# avr_programming_shield_Zif-Ken.net
KiCad netlist of a schematic drawn in EAGLE
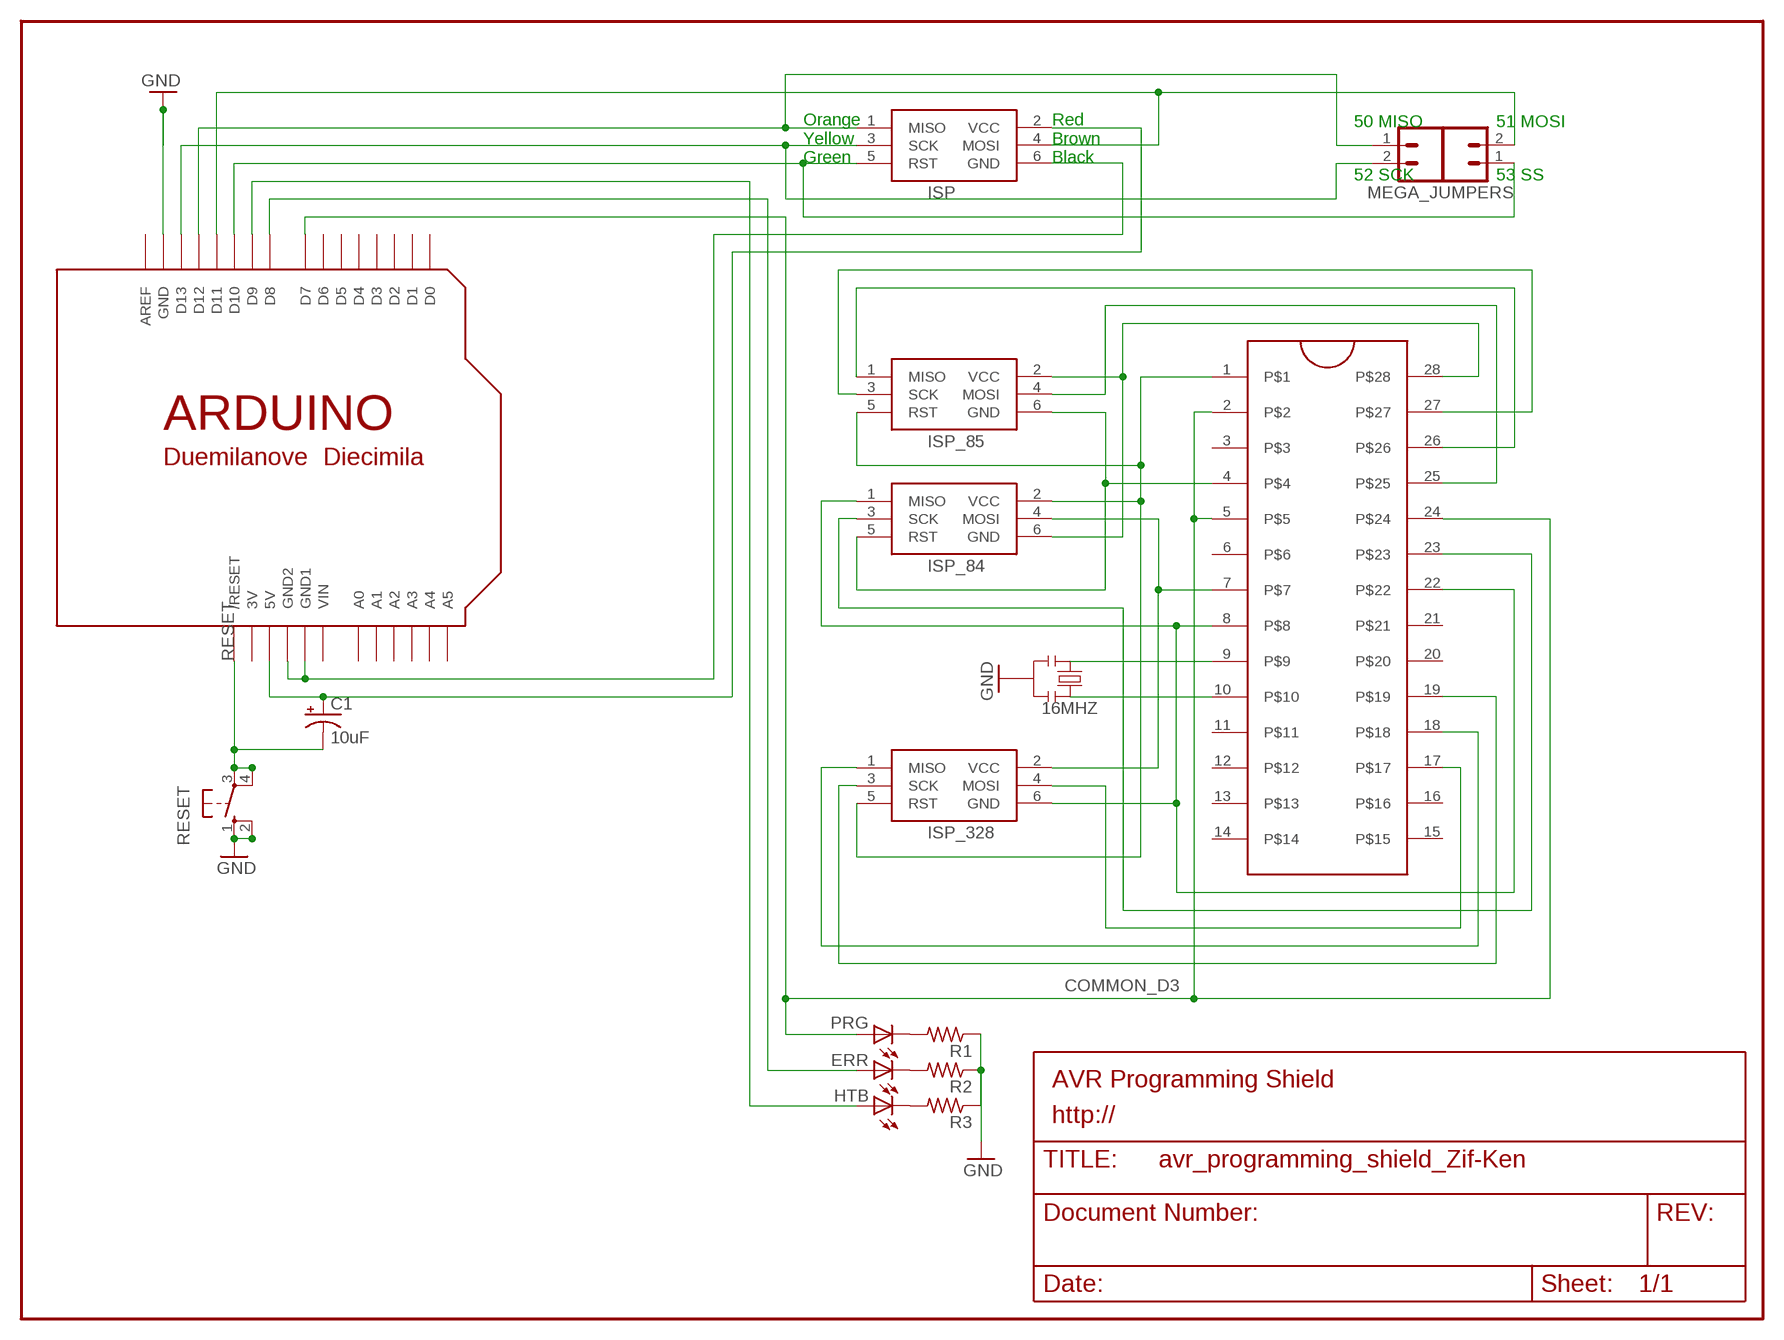
[diagram p0: schematic, sheet 1]

(export (version "E")
  (design (tool "Eeschema 10.0.6"))
  (components
    (comp (ref "16MHZ")
      (value "RESONATORPTH")
      (footprint "eagle-import:RESONATOR-PTH")
      (libsource (lib "eagle-import") (part "RESONATORPTH"))
    )
    (comp (ref "C1")
      (value "10uF")
      (footprint "eagle-import:CPOL-RADIAL-10UF-25V")
      (libsource (lib "eagle-import") (part "CAP_POLPTH2"))
    )
    (comp (ref "ERR")
      (value "LED3MM")
      (footprint "eagle-import:LED3MM")
      (libsource (lib "eagle-import") (part "LED3MM"))
    )
    (comp (ref "HTB")
      (value "LED3MM")
      (footprint "eagle-import:LED3MM")
      (libsource (lib "eagle-import") (part "LED3MM"))
    )
    (comp (ref "ISP")
      (value "AVRISP-6")
      (footprint "eagle-import:AVRISP")
      (libsource (lib "eagle-import") (part "AVRISP-6"))
    )
    (comp (ref "ISP_84")
      (value "AVRISP-6")
      (footprint "eagle-import:AVRISP")
      (libsource (lib "eagle-import") (part "AVRISP-6"))
    )
    (comp (ref "ISP_85")
      (value "AVRISP-6")
      (footprint "eagle-import:AVRISP")
      (libsource (lib "eagle-import") (part "AVRISP-6"))
    )
    (comp (ref "ISP_328")
      (value "AVRISP-6")
      (footprint "eagle-import:AVRISP")
      (libsource (lib "eagle-import") (part "AVRISP-6"))
    )
    (comp (ref "JP2")
      (value "M02PTH")
      (footprint "eagle-import:1X02")
      (libsource (lib "eagle-import") (part "M02PTH"))
    )
    (comp (ref "MEGA_JUMPERS")
      (value "M02PTH")
      (footprint "eagle-import:1X02")
      (libsource (lib "eagle-import") (part "M02PTH"))
    )
    (comp (ref "PRG")
      (value "LED3MM")
      (footprint "eagle-import:LED3MM")
      (libsource (lib "eagle-import") (part "LED3MM"))
    )
    (comp (ref "R1")
      (value "R-US_0204/2V")
      (footprint "eagle-import:0204V")
      (libsource (lib "eagle-import") (part "R-US_0204/2V"))
    )
    (comp (ref "R2")
      (value "R-US_0204/2V")
      (footprint "eagle-import:0204V")
      (libsource (lib "eagle-import") (part "R-US_0204/2V"))
    )
    (comp (ref "R3")
      (value "R-US_0204/2V")
      (footprint "eagle-import:0204V")
      (libsource (lib "eagle-import") (part "R-US_0204/2V"))
    )
    (comp (ref "RESET")
      (value "10-XX")
      (footprint "eagle-import:B3F-10XX")
      (libsource (lib "eagle-import") (part "10-XX"))
    )
    (comp (ref "U$1")
      (value "ARDUINO-NOHOLE")
      (footprint "eagle-import:ARDUINO-NOHOLE")
      (libsource (lib "eagle-import") (part "ARDUINO-NOHOLE"))
    )
    (comp (ref "U$3")
      (value "ZIFSOCKET-28-3ZIFFSOCKET-28-3")
      (footprint "eagle-import:DIL28-3-ZIF_SOCKET")
      (libsource (lib "eagle-import") (part "ZIFSOCKET-28-3ZIFFSOCKET-28-3"))
    )
  )
  (nets
    (net (code "1") (name "/3V") (class "Default")
      (node (ref "U$1") (pin "3V") (pinfunction "3V_3V") (pintype "power_in"))
    )
    (net (code "2") (name "/COMMON_D3") (class "Default")
      (node (ref "PRG") (pin "A") (pinfunction "A_A") (pintype "passive"))
      (node (ref "U$1") (pin "D7") (pinfunction "D7_D7") (pintype "bidirectional"))
      (node (ref "U$3") (pin "2") (pinfunction "P$2_2") (pintype "bidirectional"))
      (node (ref "U$3") (pin "24") (pinfunction "P$24_24") (pintype "bidirectional"))
      (node (ref "U$3") (pin "5") (pinfunction "P$5_5") (pintype "bidirectional"))
    )
    (net (code "3") (name "/RESET") (class "Default")
      (node (ref "C1") (pin "2") (pinfunction "-_2") (pintype "passive"))
      (node (ref "RESET") (pin "3") (pinfunction "P_3") (pintype "passive"))
      (node (ref "RESET") (pin "4") (pinfunction "P1_4") (pintype "passive"))
      (node (ref "U$1") (pin "RESET") (pinfunction "/RESET_RESET") (pintype "bidirectional"))
    )
    (net (code "4") (name "/VIN") (class "Default")
      (node (ref "U$1") (pin "VIN") (pinfunction "VIN_VIN") (pintype "power_in"))
    )
    (net (code "5") (name "GND") (class "Default")
      (node (ref "16MHZ") (pin "2") (pinfunction "2_2") (pintype "passive"))
      (node (ref "ISP") (pin "6") (pinfunction "GND_6") (pintype "power_in"))
      (node (ref "R1") (pin "1") (pinfunction "1_1") (pintype "passive"))
      (node (ref "R2") (pin "1") (pinfunction "1_1") (pintype "passive"))
      (node (ref "R3") (pin "1") (pinfunction "1_1") (pintype "passive"))
      (node (ref "RESET") (pin "1") (pinfunction "S_1") (pintype "passive"))
      (node (ref "RESET") (pin "2") (pinfunction "S1_2") (pintype "passive"))
      (node (ref "U$1") (pin "GND") (pinfunction "GND_GND") (pintype "power_in"))
      (node (ref "U$1") (pin "GND1") (pinfunction "GND1_GND1") (pintype "power_in"))
      (node (ref "U$1") (pin "GND2") (pinfunction "GND2_GND2") (pintype "power_in"))
    )
    (net (code "6") (name "Net-(C1-+)") (class "Default")
      (node (ref "C1") (pin "1") (pinfunction "+_1") (pintype "passive"))
      (node (ref "ISP") (pin "2") (pinfunction "VCC_2") (pintype "power_in"))
      (node (ref "U$1") (pin "5V") (pinfunction "5V_5V") (pintype "power_in"))
    )
    (net (code "7") (name "Net-(ERR-C)") (class "Default")
      (node (ref "ERR") (pin "K") (pinfunction "C_K") (pintype "passive"))
      (node (ref "R2") (pin "2") (pinfunction "2_2") (pintype "passive"))
    )
    (net (code "8") (name "Net-(ERR-PadA)") (class "Default")
      (node (ref "ERR") (pin "A") (pinfunction "A_A") (pintype "passive"))
      (node (ref "U$1") (pin "D8") (pinfunction "D8_D8") (pintype "bidirectional"))
    )
    (net (code "9") (name "Net-(HTB-C)") (class "Default")
      (node (ref "HTB") (pin "K") (pinfunction "C_K") (pintype "passive"))
      (node (ref "R3") (pin "2") (pinfunction "2_2") (pintype "passive"))
    )
    (net (code "10") (name "Net-(HTB-PadA)") (class "Default")
      (node (ref "HTB") (pin "A") (pinfunction "A_A") (pintype "passive"))
      (node (ref "U$1") (pin "D9") (pinfunction "D9_D9") (pintype "bidirectional"))
    )
    (net (code "11") (name "Net-(ISP-MISO)") (class "Default")
      (node (ref "ISP") (pin "1") (pinfunction "MISO_1") (pintype "input"))
      (node (ref "MEGA_JUMPERS") (pin "1") (pinfunction "1_1") (pintype "passive"))
      (node (ref "U$1") (pin "D12") (pinfunction "D12_D12") (pintype "bidirectional"))
    )
    (net (code "12") (name "Net-(ISP-MOSI)") (class "Default")
      (node (ref "ISP") (pin "4") (pinfunction "MOSI_4") (pintype "output"))
      (node (ref "JP2") (pin "2") (pinfunction "2_2") (pintype "passive"))
      (node (ref "U$1") (pin "D11") (pinfunction "D11_D11") (pintype "bidirectional"))
    )
    (net (code "13") (name "Net-(ISP-RST)") (class "Default")
      (node (ref "ISP") (pin "5") (pinfunction "RST_5") (pintype "output"))
      (node (ref "JP2") (pin "1") (pinfunction "1_1") (pintype "passive"))
      (node (ref "U$1") (pin "D10") (pinfunction "D10_D10") (pintype "bidirectional"))
    )
    (net (code "14") (name "Net-(ISP-SCK)") (class "Default")
      (node (ref "ISP") (pin "3") (pinfunction "SCK_3") (pintype "output"))
      (node (ref "MEGA_JUMPERS") (pin "2") (pinfunction "2_2") (pintype "passive"))
      (node (ref "U$1") (pin "D13") (pinfunction "D13_D13") (pintype "bidirectional"))
    )
    (net (code "15") (name "Net-(ISP_84-GND)") (class "Default")
      (node (ref "ISP_84") (pin "6") (pinfunction "GND_6") (pintype "power_in"))
      (node (ref "ISP_85") (pin "2") (pinfunction "VCC_2") (pintype "power_in"))
      (node (ref "U$3") (pin "28") (pinfunction "P$28_28") (pintype "bidirectional"))
    )
    (net (code "16") (name "Net-(ISP_84-RST)") (class "Default")
      (node (ref "ISP_84") (pin "5") (pinfunction "RST_5") (pintype "output"))
      (node (ref "ISP_85") (pin "6") (pinfunction "GND_6") (pintype "power_in"))
      (node (ref "U$3") (pin "4") (pinfunction "P$4_4") (pintype "bidirectional"))
    )
    (net (code "17") (name "Net-(ISP_84-SCK)") (class "Default")
      (node (ref "ISP_84") (pin "3") (pinfunction "SCK_3") (pintype "output"))
      (node (ref "U$3") (pin "23") (pinfunction "P$23_23") (pintype "bidirectional"))
    )
    (net (code "18") (name "Net-(ISP_85-MISO)") (class "Default")
      (node (ref "ISP_85") (pin "1") (pinfunction "MISO_1") (pintype "input"))
      (node (ref "U$3") (pin "26") (pinfunction "P$26_26") (pintype "bidirectional"))
    )
    (net (code "19") (name "Net-(ISP_85-MOSI)") (class "Default")
      (node (ref "ISP_85") (pin "4") (pinfunction "MOSI_4") (pintype "output"))
      (node (ref "U$3") (pin "25") (pinfunction "P$25_25") (pintype "bidirectional"))
    )
    (net (code "20") (name "Net-(ISP_85-SCK)") (class "Default")
      (node (ref "ISP_85") (pin "3") (pinfunction "SCK_3") (pintype "output"))
      (node (ref "U$3") (pin "27") (pinfunction "P$27_27") (pintype "bidirectional"))
    )
    (net (code "21") (name "Net-(ISP_328-GND)") (class "Default")
      (node (ref "ISP_328") (pin "6") (pinfunction "GND_6") (pintype "power_in"))
      (node (ref "ISP_84") (pin "1") (pinfunction "MISO_1") (pintype "input"))
      (node (ref "U$3") (pin "22") (pinfunction "P$22_22") (pintype "bidirectional"))
      (node (ref "U$3") (pin "8") (pinfunction "P$8_8") (pintype "bidirectional"))
    )
    (net (code "22") (name "Net-(ISP_328-MISO)") (class "Default")
      (node (ref "ISP_328") (pin "1") (pinfunction "MISO_1") (pintype "input"))
      (node (ref "U$3") (pin "18") (pinfunction "P$18_18") (pintype "bidirectional"))
    )
    (net (code "23") (name "Net-(ISP_328-MOSI)") (class "Default")
      (node (ref "ISP_328") (pin "4") (pinfunction "MOSI_4") (pintype "output"))
      (node (ref "U$3") (pin "17") (pinfunction "P$17_17") (pintype "bidirectional"))
    )
    (net (code "24") (name "Net-(ISP_328-RST)") (class "Default")
      (node (ref "ISP_328") (pin "5") (pinfunction "RST_5") (pintype "output"))
      (node (ref "ISP_84") (pin "2") (pinfunction "VCC_2") (pintype "power_in"))
      (node (ref "ISP_85") (pin "5") (pinfunction "RST_5") (pintype "output"))
      (node (ref "U$3") (pin "1") (pinfunction "P$1_1") (pintype "bidirectional"))
    )
    (net (code "25") (name "Net-(ISP_328-SCK)") (class "Default")
      (node (ref "ISP_328") (pin "3") (pinfunction "SCK_3") (pintype "output"))
      (node (ref "U$3") (pin "19") (pinfunction "P$19_19") (pintype "bidirectional"))
    )
    (net (code "26") (name "Net-(ISP_328-VCC)") (class "Default")
      (node (ref "ISP_328") (pin "2") (pinfunction "VCC_2") (pintype "power_in"))
      (node (ref "ISP_84") (pin "4") (pinfunction "MOSI_4") (pintype "output"))
      (node (ref "U$3") (pin "7") (pinfunction "P$7_7") (pintype "bidirectional"))
    )
    (net (code "27") (name "Net-(PRG-C)") (class "Default")
      (node (ref "PRG") (pin "K") (pinfunction "C_K") (pintype "passive"))
      (node (ref "R1") (pin "2") (pinfunction "2_2") (pintype "passive"))
    )
    (net (code "28") (name "Net-(U$3-P$9)") (class "Default")
      (node (ref "16MHZ") (pin "1") (pinfunction "1_1") (pintype "passive"))
      (node (ref "U$3") (pin "9") (pinfunction "P$9_9") (pintype "bidirectional"))
    )
    (net (code "29") (name "Net-(U$3-P$10)") (class "Default")
      (node (ref "16MHZ") (pin "3") (pinfunction "3_3") (pintype "passive"))
      (node (ref "U$3") (pin "10") (pinfunction "P$10_10") (pintype "bidirectional"))
    )
    (net (code "30") (name "unconnected-(U$1-PadA0)") (class "Default")
      (node (ref "U$1") (pin "A0") (pinfunction "A0_A0") (pintype "bidirectional"))
    )
    (net (code "31") (name "unconnected-(U$1-PadA1)") (class "Default")
      (node (ref "U$1") (pin "A1") (pinfunction "A1_A1") (pintype "bidirectional"))
    )
    (net (code "32") (name "unconnected-(U$1-PadA2)") (class "Default")
      (node (ref "U$1") (pin "A2") (pinfunction "A2_A2") (pintype "bidirectional"))
    )
    (net (code "33") (name "unconnected-(U$1-PadA3)") (class "Default")
      (node (ref "U$1") (pin "A3") (pinfunction "A3_A3") (pintype "bidirectional"))
    )
    (net (code "34") (name "unconnected-(U$1-PadA4)") (class "Default")
      (node (ref "U$1") (pin "A4") (pinfunction "A4_A4") (pintype "bidirectional"))
    )
    (net (code "35") (name "unconnected-(U$1-PadA5)") (class "Default")
      (node (ref "U$1") (pin "A5") (pinfunction "A5_A5") (pintype "bidirectional"))
    )
    (net (code "36") (name "unconnected-(U$1-PadAREF)") (class "Default")
      (node (ref "U$1") (pin "AREF") (pinfunction "AREF_AREF") (pintype "bidirectional"))
    )
    (net (code "37") (name "unconnected-(U$1-PadD0)") (class "Default")
      (node (ref "U$1") (pin "D0") (pinfunction "D0_D0") (pintype "bidirectional"))
    )
    (net (code "38") (name "unconnected-(U$1-PadD1)") (class "Default")
      (node (ref "U$1") (pin "D1") (pinfunction "D1_D1") (pintype "bidirectional"))
    )
    (net (code "39") (name "unconnected-(U$1-PadD2)") (class "Default")
      (node (ref "U$1") (pin "D2") (pinfunction "D2_D2") (pintype "bidirectional"))
    )
    (net (code "40") (name "unconnected-(U$1-PadD3)") (class "Default")
      (node (ref "U$1") (pin "D3") (pinfunction "D3_D3") (pintype "bidirectional"))
    )
    (net (code "41") (name "unconnected-(U$1-PadD4)") (class "Default")
      (node (ref "U$1") (pin "D4") (pinfunction "D4_D4") (pintype "bidirectional"))
    )
    (net (code "42") (name "unconnected-(U$1-PadD5)") (class "Default")
      (node (ref "U$1") (pin "D5") (pinfunction "D5_D5") (pintype "bidirectional"))
    )
    (net (code "43") (name "unconnected-(U$1-PadD6)") (class "Default")
      (node (ref "U$1") (pin "D6") (pinfunction "D6_D6") (pintype "bidirectional"))
    )
    (net (code "44") (name "unconnected-(U$3-P$3-Pad3)") (class "Default")
      (node (ref "U$3") (pin "3") (pinfunction "P$3_3") (pintype "bidirectional"))
    )
    (net (code "45") (name "unconnected-(U$3-P$6-Pad6)") (class "Default")
      (node (ref "U$3") (pin "6") (pinfunction "P$6_6") (pintype "bidirectional"))
    )
    (net (code "46") (name "unconnected-(U$3-P$11-Pad11)") (class "Default")
      (node (ref "U$3") (pin "11") (pinfunction "P$11_11") (pintype "bidirectional"))
    )
    (net (code "47") (name "unconnected-(U$3-P$12-Pad12)") (class "Default")
      (node (ref "U$3") (pin "12") (pinfunction "P$12_12") (pintype "bidirectional"))
    )
    (net (code "48") (name "unconnected-(U$3-P$13-Pad13)") (class "Default")
      (node (ref "U$3") (pin "13") (pinfunction "P$13_13") (pintype "bidirectional"))
    )
    (net (code "49") (name "unconnected-(U$3-P$14-Pad14)") (class "Default")
      (node (ref "U$3") (pin "14") (pinfunction "P$14_14") (pintype "bidirectional"))
    )
    (net (code "50") (name "unconnected-(U$3-P$15-Pad15)") (class "Default")
      (node (ref "U$3") (pin "15") (pinfunction "P$15_15") (pintype "bidirectional"))
    )
    (net (code "51") (name "unconnected-(U$3-P$16-Pad16)") (class "Default")
      (node (ref "U$3") (pin "16") (pinfunction "P$16_16") (pintype "bidirectional"))
    )
    (net (code "52") (name "unconnected-(U$3-P$20-Pad20)") (class "Default")
      (node (ref "U$3") (pin "20") (pinfunction "P$20_20") (pintype "bidirectional"))
    )
    (net (code "53") (name "unconnected-(U$3-P$21-Pad21)") (class "Default")
      (node (ref "U$3") (pin "21") (pinfunction "P$21_21") (pintype "bidirectional"))
    )
  )
)
